# lipolski-control.net
KiCad netlist of a schematic drawn in EAGLE
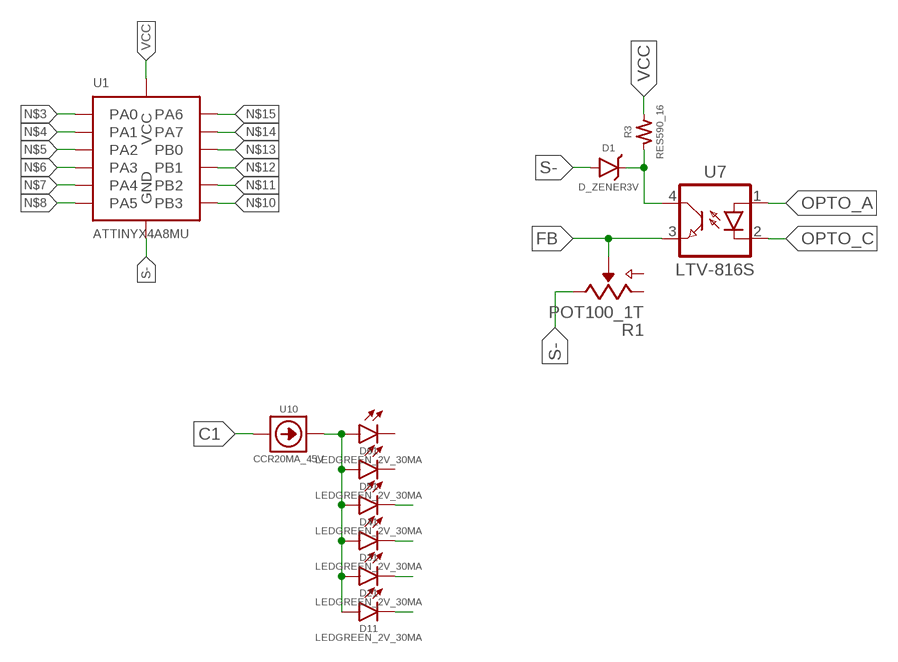
[diagram p0: schematic, sheet 1]

(export (version "E")
  (design (tool "Eeschema 10.0.6"))
  (components
    (comp (ref "D1")
      (value "D_ZENER3V")
      (footprint "eagle-import:SOT23-3")
      (fields
        (field (name "DIGIKEY_PART_#") "BZX84B3V0-FDICT-ND")
        (field (name "MANUFACTURER") "Diodes Incorporated")
        (field (name "MFG_PART_#") "BZX84B3V0-7-F")
      )
      (libsource (lib "eagle-import") (part "D_ZENER3V"))
    )
    (comp (ref "D11")
      (value "LEDGREEN_2V_30MA")
      (footprint "eagle-import:0603+")
      (fields
        (field (name "DIGIKEY_PART_#") "160-1435-1-ND")
        (field (name "MANUFACTURER") "Lite-On Inc.")
        (field (name "MFG_PART_#") "LTST-C190KGKT")
      )
      (libsource (lib "eagle-import") (part "LEDGREEN_2V_30MA"))
    )
    (comp (ref "D21")
      (value "LEDGREEN_2V_30MA")
      (footprint "eagle-import:0603+")
      (fields
        (field (name "DIGIKEY_PART_#") "160-1435-1-ND")
        (field (name "MANUFACTURER") "Lite-On Inc.")
        (field (name "MFG_PART_#") "LTST-C190KGKT")
      )
      (libsource (lib "eagle-import") (part "LEDGREEN_2V_30MA"))
    )
    (comp (ref "D31")
      (value "LEDGREEN_2V_30MA")
      (footprint "eagle-import:0603+")
      (fields
        (field (name "DIGIKEY_PART_#") "160-1435-1-ND")
        (field (name "MANUFACTURER") "Lite-On Inc.")
        (field (name "MFG_PART_#") "LTST-C190KGKT")
      )
      (libsource (lib "eagle-import") (part "LEDGREEN_2V_30MA"))
    )
    (comp (ref "D41")
      (value "LEDGREEN_2V_30MA")
      (footprint "eagle-import:0603+")
      (fields
        (field (name "DIGIKEY_PART_#") "160-1435-1-ND")
        (field (name "MANUFACTURER") "Lite-On Inc.")
        (field (name "MFG_PART_#") "LTST-C190KGKT")
      )
      (libsource (lib "eagle-import") (part "LEDGREEN_2V_30MA"))
    )
    (comp (ref "D51")
      (value "LEDGREEN_2V_30MA")
      (footprint "eagle-import:0603+")
      (fields
        (field (name "DIGIKEY_PART_#") "160-1435-1-ND")
        (field (name "MANUFACTURER") "Lite-On Inc.")
        (field (name "MFG_PART_#") "LTST-C190KGKT")
      )
      (libsource (lib "eagle-import") (part "LEDGREEN_2V_30MA"))
    )
    (comp (ref "D61")
      (value "LEDGREEN_2V_30MA")
      (footprint "eagle-import:0603+")
      (fields
        (field (name "DIGIKEY_PART_#") "160-1435-1-ND")
        (field (name "MANUFACTURER") "Lite-On Inc.")
        (field (name "MFG_PART_#") "LTST-C190KGKT")
      )
      (libsource (lib "eagle-import") (part "LEDGREEN_2V_30MA"))
    )
    (comp (ref "R1")
      (value "POT100_1T")
      (footprint "eagle-import:ST-4EA")
      (fields
        (field (name "DIGIKEY_PART_#") "ST4ETA101CT-ND")
        (field (name "MANUFACTURER") "Copal Electronics Inc.")
        (field (name "MFG_PART_#") "ST4ETA101")
      )
      (libsource (lib "eagle-import") (part "POT100_1T"))
    )
    (comp (ref "R3")
      (value "RES590_16")
      (footprint "eagle-import:0402")
      (fields
        (field (name "DIGIKEY_PART_#") "541-590LCT-ND")
        (field (name "MANUFACTURER") "Vishay Dale")
        (field (name "MFG_PART_#") "CRCW0402590RFKED")
      )
      (libsource (lib "eagle-import") (part "RES590_16"))
    )
    (comp (ref "U1")
      (value "ATTINYX4A8MU")
      (footprint "eagle-import:ATTINYX4A")
      (fields
        (field (name "DIGIKEY_PART_#") "ATTINY84A-MU-ND")
        (field (name "MANUFACTURER") "Atmel")
        (field (name "MFG_PART_#") "ATTINY84A-MU")
      )
      (libsource (lib "eagle-import") (part "ATTINYX4A8MU"))
    )
    (comp (ref "U7")
      (value "LTV-816S")
      (footprint "eagle-import:4-OPTO-1")
      (fields (field (name "DIGIKEY_PART_#") "160-1361-5-ND") (field (name "MANUFACTURER") "Lite-On Inc."))
      (libsource (lib "eagle-import") (part "LTV-816S"))
    )
    (comp (ref "U10")
      (value "CCR20MA_45V")
      (footprint "eagle-import:SOD-123")
      (fields
        (field (name "DIGIKEY_PART_#") "NSI45020T1GOSCT-ND")
        (field (name "MANUFACTURER") "ON Semiconductor")
        (field (name "MFG_PART_#") "NSI45020T1G")
      )
      (libsource (lib "eagle-import") (part "CCR20MA_45V"))
    )
  )
  (nets
    (net (code "1") (name "C1") (class "Default")
      (node (ref "U10") (pin "A") (pinfunction "A_A") (pintype "passive"))
    )
    (net (code "2") (name "FB") (class "Default")
      (node (ref "R1") (pin "2") (pinfunction "S_2") (pintype "passive"))
      (node (ref "U7") (pin "3") (pinfunction "E_3") (pintype "passive"))
    )
    (net (code "3") (name "N$3") (class "Default")
      (node (ref "U1") (pin "5") (pinfunction "PA0_5") (pintype "passive"))
    )
    (net (code "4") (name "N$4") (class "Default")
      (node (ref "U1") (pin "4") (pinfunction "PA1_4") (pintype "passive"))
    )
    (net (code "5") (name "N$5") (class "Default")
      (node (ref "U1") (pin "3") (pinfunction "PA2_3") (pintype "passive"))
    )
    (net (code "6") (name "N$6") (class "Default")
      (node (ref "U1") (pin "2") (pinfunction "PA3_2") (pintype "passive"))
    )
    (net (code "7") (name "N$7") (class "Default")
      (node (ref "U1") (pin "1") (pinfunction "PA4_1") (pintype "passive"))
    )
    (net (code "8") (name "N$8") (class "Default")
      (node (ref "U1") (pin "20") (pinfunction "PA5_20") (pintype "passive"))
    )
    (net (code "9") (name "N$10") (class "Default")
      (node (ref "U1") (pin "13") (pinfunction "PB3_13") (pintype "passive"))
    )
    (net (code "10") (name "N$11") (class "Default")
      (node (ref "U1") (pin "14") (pinfunction "PB2_14") (pintype "passive"))
    )
    (net (code "11") (name "N$12") (class "Default")
      (node (ref "U1") (pin "12") (pinfunction "PB1_12") (pintype "passive"))
    )
    (net (code "12") (name "N$13") (class "Default")
      (node (ref "U1") (pin "11") (pinfunction "PB0_11") (pintype "passive"))
    )
    (net (code "13") (name "N$14") (class "Default")
      (node (ref "U1") (pin "15") (pinfunction "PA7_15") (pintype "passive"))
    )
    (net (code "14") (name "N$15") (class "Default")
      (node (ref "U1") (pin "16") (pinfunction "PA6_16") (pintype "passive"))
    )
    (net (code "15") (name "Net-(D1-C)") (class "Default")
      (node (ref "D1") (pin "3") (pinfunction "C_3") (pintype "passive"))
      (node (ref "R3") (pin "1") (pinfunction "1_1") (pintype "passive"))
      (node (ref "U7") (pin "4") (pinfunction "C_4") (pintype "passive"))
    )
    (net (code "16") (name "Net-(D11-PadA)") (class "Default")
      (node (ref "D11") (pin "A") (pinfunction "A_A") (pintype "passive"))
      (node (ref "D21") (pin "A") (pinfunction "A_A") (pintype "passive"))
      (node (ref "D31") (pin "A") (pinfunction "A_A") (pintype "passive"))
      (node (ref "D41") (pin "A") (pinfunction "A_A") (pintype "passive"))
      (node (ref "D51") (pin "A") (pinfunction "A_A") (pintype "passive"))
      (node (ref "D61") (pin "A") (pinfunction "A_A") (pintype "passive"))
      (node (ref "U10") (pin "C") (pinfunction "C_C") (pintype "passive"))
    )
    (net (code "17") (name "OPTO_A") (class "Default")
      (node (ref "U7") (pin "1") (pinfunction "A_1") (pintype "passive"))
    )
    (net (code "18") (name "OPTO_C") (class "Default")
      (node (ref "U7") (pin "2") (pinfunction "K_2") (pintype "passive"))
    )
    (net (code "19") (name "S-") (class "Default")
      (node (ref "D1") (pin "1") (pinfunction "A_1") (pintype "passive"))
      (node (ref "R1") (pin "3") (pinfunction "E_3") (pintype "passive"))
      (node (ref "U1") (pin "8") (pinfunction "GND_8") (pintype "passive"))
      (node (ref "U1") (pin "PAD") (pinfunction "GND_PAD") (pintype "passive"))
    )
    (net (code "20") (name "VCC") (class "Default")
      (node (ref "R3") (pin "2") (pinfunction "2_2") (pintype "passive"))
      (node (ref "U1") (pin "9") (pinfunction "VCC_9") (pintype "passive"))
    )
    (net (code "21") (name "unconnected-(D11-PadC)") (class "Default")
      (node (ref "D11") (pin "C") (pinfunction "C_C") (pintype "passive"))
    )
    (net (code "22") (name "unconnected-(D21-PadC)") (class "Default")
      (node (ref "D21") (pin "C") (pinfunction "C_C") (pintype "passive"))
    )
    (net (code "23") (name "unconnected-(D31-PadC)") (class "Default")
      (node (ref "D31") (pin "C") (pinfunction "C_C") (pintype "passive"))
    )
    (net (code "24") (name "unconnected-(D41-PadC)") (class "Default")
      (node (ref "D41") (pin "C") (pinfunction "C_C") (pintype "passive"))
    )
    (net (code "25") (name "unconnected-(D51-PadC)") (class "Default")
      (node (ref "D51") (pin "C") (pinfunction "C_C") (pintype "passive"))
    )
    (net (code "26") (name "unconnected-(D61-PadC)") (class "Default")
      (node (ref "D61") (pin "C") (pinfunction "C_C") (pintype "passive"))
    )
    (net (code "27") (name "unconnected-(R1-A-Pad1)") (class "Default")
      (node (ref "R1") (pin "1") (pinfunction "A_1") (pintype "passive"))
    )
  )
)
